# PA_stage_2.net
KiCad netlist of a schematic drawn in Altium Designer
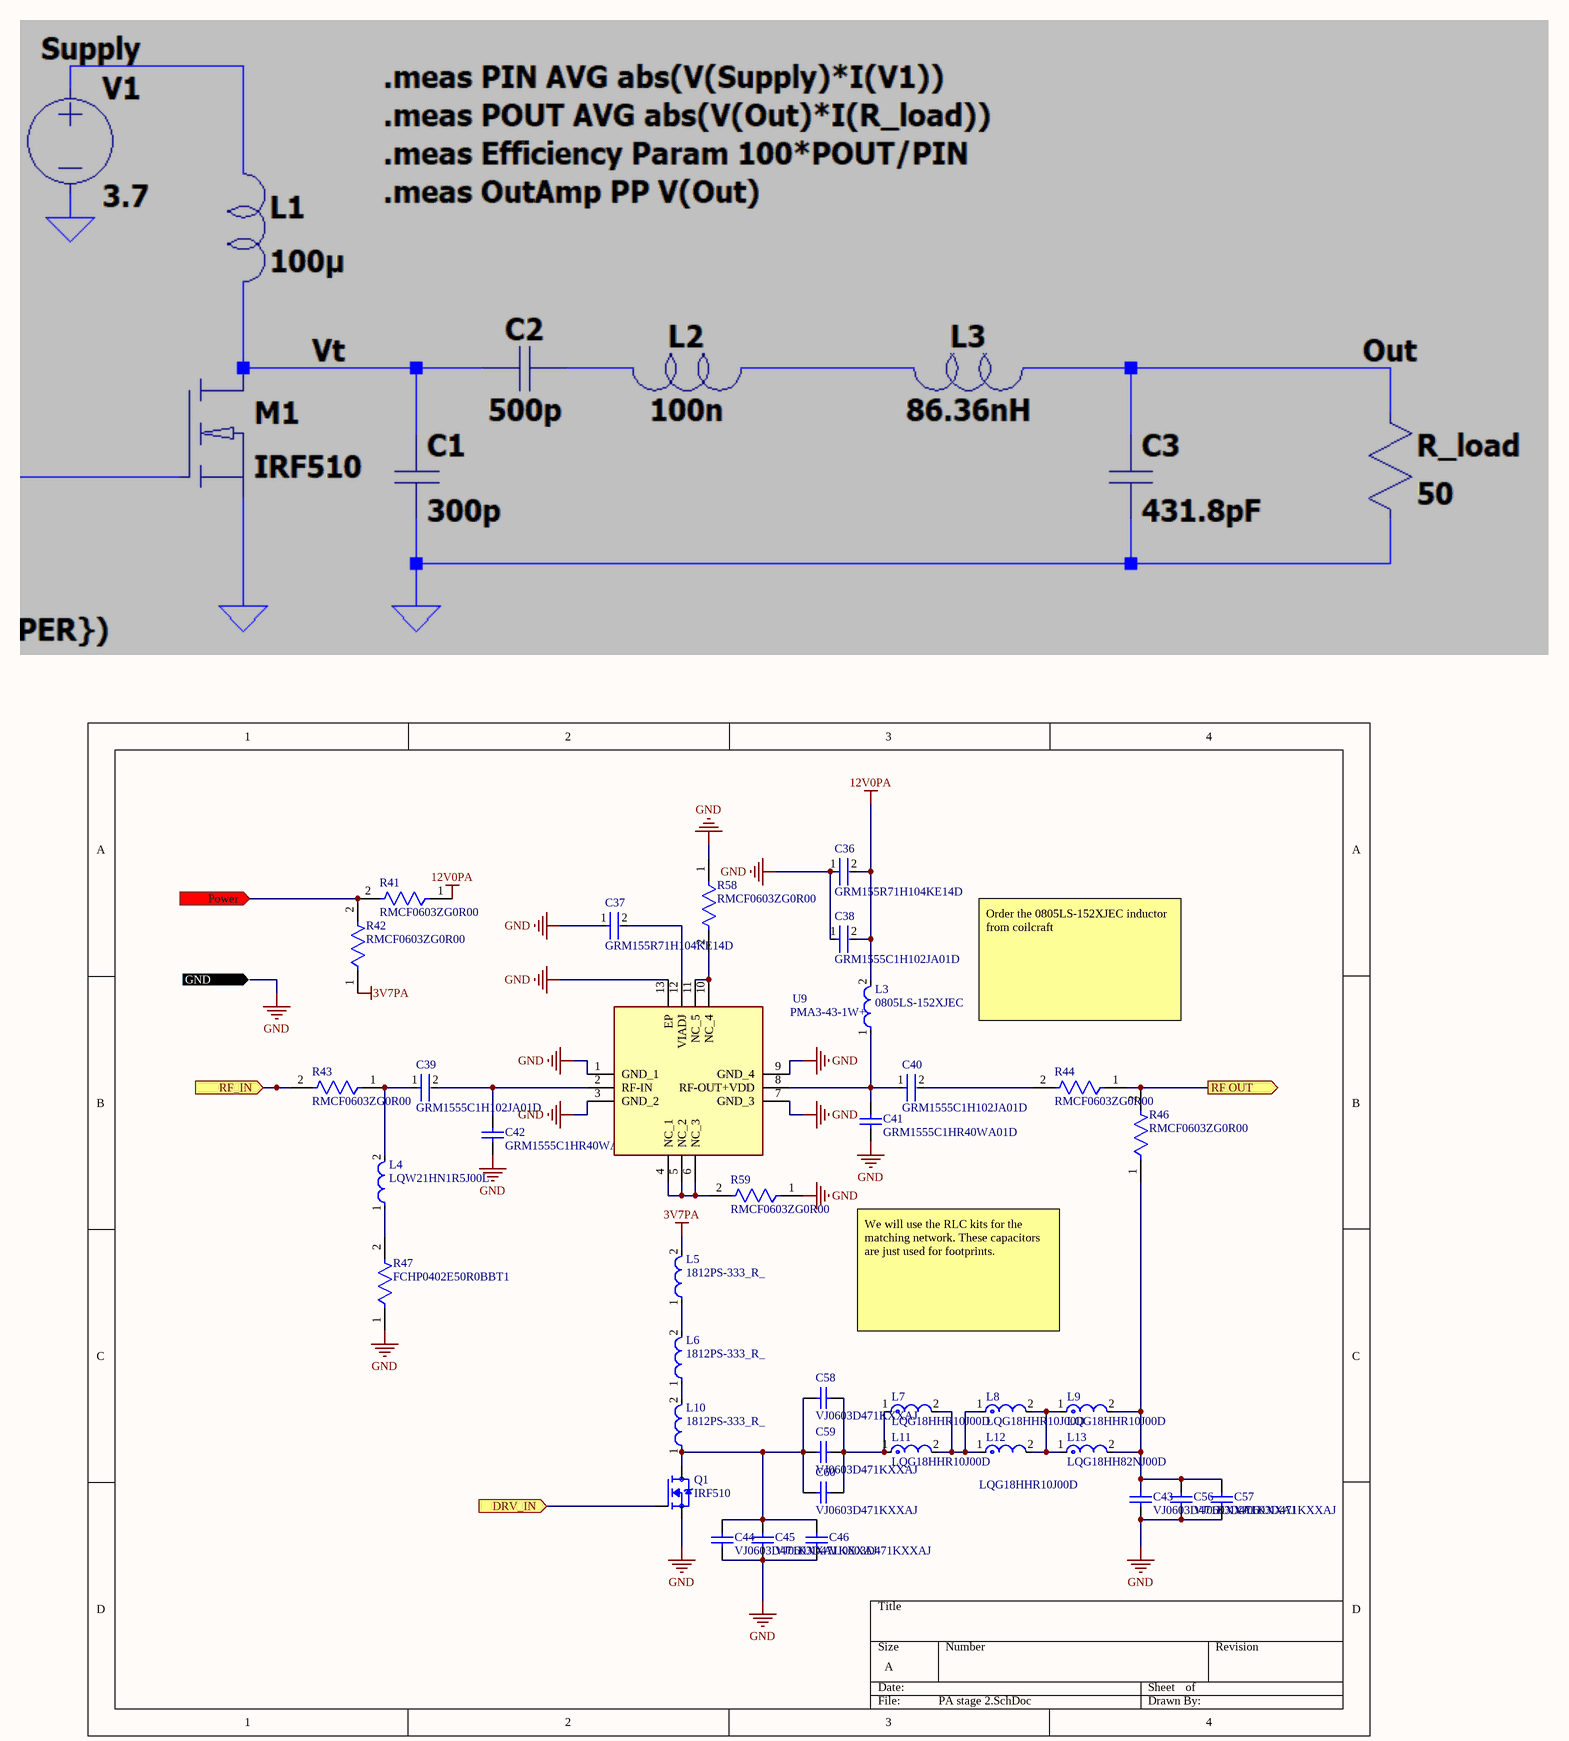
[diagram p0: PA stage 2.SchDoc]

(export (version "E")
  (design (tool "Eeschema 10.0.6"))
  (components
    (comp (ref "C36")
      (value "GRM155R71H104KE14D")
      (footprint "FP-GRM155-0_05-IPC_B")
      (description "Chip Multilayer Ceramic Capacitors for General Purpose, 0402, 0.10uF, X7R, 15%, 10%, 50V")
      (fields (field (name "VOLTAGE") "50V") (field (name "TOLERANCE") "10%"))
      (libsource (lib "Altium Content Vault") (part "02cd4be3c70576c341d710602a673aa"))
    )
    (comp (ref "C37")
      (value "GRM155R71H104KE14D")
      (footprint "FP-GRM155-0_05-IPC_B")
      (description "Chip Multilayer Ceramic Capacitors for General Purpose, 0402, 0.10uF, X7R, 15%, 10%, 50V")
      (fields (field (name "VOLTAGE") "50V") (field (name "TOLERANCE") "10%"))
      (libsource (lib "Altium Content Vault") (part "02cd4be3c70576c341d710602a673aa"))
    )
    (comp (ref "C38")
      (value "GRM1555C1H102JA01D")
      (footprint "FP-GRM155-0_05-IPC_B")
      (description "Chip Multilayer Ceramic Capacitors for General Purpose, 0402, 1000pF, C0G, 30ppm/°C, 5%, 50V")
      (fields (field (name "TOLERANCE") "5%") (field (name "VOLTAGE") "50V"))
      (libsource (lib "Altium Content Vault") (part "02cd4be3c70576c341d710602a673aa"))
    )
    (comp (ref "C39")
      (value "GRM1555C1H102JA01D")
      (footprint "FP-GRM155-0_05-IPC_B")
      (description "Chip Multilayer Ceramic Capacitors for General Purpose, 0402, 1000pF, C0G, 30ppm/°C, 5%, 50V")
      (fields (field (name "TOLERANCE") "5%") (field (name "VOLTAGE") "50V"))
      (libsource (lib "Altium Content Vault") (part "02cd4be3c70576c341d710602a673aa"))
    )
    (comp (ref "C40")
      (value "GRM1555C1H102JA01D")
      (footprint "FP-GRM155-0_05-IPC_B")
      (description "Chip Multilayer Ceramic Capacitors for General Purpose, 0402, 1000pF, C0G, 30ppm/°C, 5%, 50V")
      (fields (field (name "TOLERANCE") "5%") (field (name "VOLTAGE") "50V"))
      (libsource (lib "Altium Content Vault") (part "02cd4be3c70576c341d710602a673aa"))
    )
    (comp (ref "C41")
      (value "GRM1555C1HR40WA01D")
      (footprint "CAPC1005X55X25LL05T10")
      (fields (field (name "MANUFACTURER") "Murata"))
      (libsource (lib "Altium Content Vault") (part "CAP"))
    )
    (comp (ref "C42")
      (value "GRM1555C1HR40WA01D")
      (footprint "CAPC1005X55X25LL05T10")
      (fields (field (name "MANUFACTURER") "Murata"))
      (libsource (lib "Altium Content Vault") (part "CAP"))
    )
    (comp (ref "C43")
      (value "VJ0603D471KXXAJ")
      (footprint "CAPC1608X92X38LL15T08")
      (fields (field (name "MANUFACTURER") "Vitramon"))
      (libsource (lib "Altium Content Vault") (part "CAP"))
    )
    (comp (ref "C44")
      (value "VJ0603D471KXXAJ")
      (footprint "CAPC1608X92X38LL15T08")
      (fields (field (name "MANUFACTURER") "Vitramon"))
      (libsource (lib "Altium Content Vault") (part "CAP"))
    )
    (comp (ref "C45")
      (value "VJ0603D471KXXAJ")
      (footprint "CAPC1608X92X38LL15T08")
      (fields (field (name "MANUFACTURER") "Vitramon"))
      (libsource (lib "Altium Content Vault") (part "CAP"))
    )
    (comp (ref "C46")
      (value "VJ0603D471KXXAJ")
      (footprint "CAPC1608X92X38LL15T08")
      (fields (field (name "MANUFACTURER") "Vitramon"))
      (libsource (lib "Altium Content Vault") (part "CAP"))
    )
    (comp (ref "C56")
      (value "VJ0603D471KXXAJ")
      (footprint "CAPC1608X92X38LL15T08")
      (fields (field (name "MANUFACTURER") "Vitramon"))
      (libsource (lib "Altium Content Vault") (part "CAP"))
    )
    (comp (ref "C57")
      (value "VJ0603D471KXXAJ")
      (footprint "CAPC1608X92X38LL15T08")
      (fields (field (name "MANUFACTURER") "Vitramon"))
      (libsource (lib "Altium Content Vault") (part "CAP"))
    )
    (comp (ref "C58")
      (value "VJ0603D471KXXAJ")
      (footprint "CAPC1608X92X38LL15T08")
      (fields (field (name "MANUFACTURER") "Vitramon"))
      (libsource (lib "Altium Content Vault") (part "CAP"))
    )
    (comp (ref "C59")
      (value "VJ0603D471KXXAJ")
      (footprint "CAPC1608X92X38LL15T08")
      (fields (field (name "MANUFACTURER") "Vitramon"))
      (libsource (lib "Altium Content Vault") (part "CAP"))
    )
    (comp (ref "C60")
      (value "VJ0603D471KXXAJ")
      (footprint "CAPC1608X92X38LL15T08")
      (fields (field (name "MANUFACTURER") "Vitramon"))
      (libsource (lib "Altium Content Vault") (part "CAP"))
    )
    (comp (ref "L3")
      (value "0805LS-152XJEC")
      (footprint "FP-LQW21HN_00-MFG")
      (description "0805LS-152XJEC Coilcraft")
      (fields (field (name "TOLERANCE") "5%"))
      (libsource (lib "Altium Content Vault") (part "725321dda6339637d4d059423bc1c3c"))
    )
    (comp (ref "L4")
      (value "LQW21HN1R5J00L")
      (footprint "FP-LQW21HN_00-MFG")
      (description "Wire Wound Ferrite type RF Inuctor 1.5uH ±5% 85mA 5.33Ω 0805 (2012)")
      (fields (field (name "TOLERANCE") "5%"))
      (libsource (lib "Altium Content Vault") (part "725321dda6339637d4d059423bc1c3c"))
    )
    (comp (ref "L5")
      (value "1812PS-333_R_")
      (footprint "FP-1812PS-MFG")
      (description "1812PS-333_R_Coilcraft")
      (fields (field (name "TOLERANCE") "5%"))
      (libsource (lib "Altium Content Vault") (part "725321dda6339637d4d059423bc1c3c"))
    )
    (comp (ref "L6")
      (value "1812PS-333_R_")
      (footprint "FP-1812PS-MFG")
      (description "1812PS-333_R_Coilcraft")
      (fields (field (name "TOLERANCE") "5%"))
      (libsource (lib "Altium Content Vault") (part "725321dda6339637d4d059423bc1c3c"))
    )
    (comp (ref "L7")
      (value "LQG18HHR10J00D")
      (footprint "FP-LQG18HH_00-MFG")
      (description "Multilayer type Inductor for Automotive 100nH ±5% 0.9Ω 300mA 0603")
      (libsource (lib "Altium Content Vault") (part "4cc4b267dca4c8e51f7102f422741d8"))
    )
    (comp (ref "L8")
      (value "LQG18HHR10J00D")
      (footprint "FP-LQG18HH_00-MFG")
      (description "Multilayer type Inductor for Automotive 100nH ±5% 0.9Ω 300mA 0603")
      (libsource (lib "Altium Content Vault") (part "4cc4b267dca4c8e51f7102f422741d8"))
    )
    (comp (ref "L9")
      (value "LQG18HHR10J00D")
      (footprint "FP-LQG18HH_00-MFG")
      (description "Multilayer type Inductor for Automotive 100nH ±5% 0.9Ω 300mA 0603")
      (libsource (lib "Altium Content Vault") (part "4cc4b267dca4c8e51f7102f422741d8"))
    )
    (comp (ref "L10")
      (value "1812PS-333_R_")
      (footprint "FP-1812PS-MFG")
      (description "1812PS-333_R_ Coilcraft")
      (fields (field (name "TOLERANCE") "5%"))
      (libsource (lib "Altium Content Vault") (part "725321dda6339637d4d059423bc1c3c"))
    )
    (comp (ref "L11")
      (value "LQG18HHR10J00D")
      (footprint "FP-LQG18HH_00-MFG")
      (description "Multilayer type Inductor for Automotive 100nH ±5% 0.9Ω 300mA 0603")
      (libsource (lib "Altium Content Vault") (part "4cc4b267dca4c8e51f7102f422741d8"))
    )
    (comp (ref "L12")
      (value "LQG18HHR10J00D")
      (footprint "FP-LQG18HH_00-MFG")
      (description "Multilayer type Inductor for Automotive 100nH ±5% 0.9Ω 300mA 0603")
      (libsource (lib "Altium Content Vault") (part "4cc4b267dca4c8e51f7102f422741d8"))
    )
    (comp (ref "L13")
      (value "LQG18HH82NJ00D")
      (footprint "FP-LQG18HH_00-IPC_B")
      (description "Multilayer type Inductor for Automotive 82nH ±5% 0.85Ω 300mA 0603")
      (libsource (lib "Altium Content Vault") (part "4cc4b267dca4c8e51f7102f422741d8"))
    )
    (comp (ref "Q1")
      (value "IRF510")
      (footprint "TO254P1051X465X1931-3")
      (description "N-Channel 100 V 5.6A (Tc) 3.7W (Ta), 43W (Tc) Surface Mount DÂ²PAK (TO-263)")
      (fields (field (name "MF") "Vishay Siliconix"))
      (libsource (lib "IRF510") (part "IRF510"))
    )
    (comp (ref "R41")
      (value "RMCF0603ZG0R00")
      (footprint "FP-RMCF0603-IPC_B")
      (description "0Ω ±0 0.1W 0603 Thick Film Chip Resistor AEC-Q200 compliant")
      (libsource (lib "Altium Content Vault") (part "1029c3af85768c4190bb7ad29bc67b5"))
    )
    (comp (ref "R42")
      (value "RMCF0603ZG0R00")
      (footprint "FP-RMCF0603-IPC_B")
      (description "0Ω ±0 0.1W 0603 Thick Film Chip Resistor AEC-Q200 compliant")
      (libsource (lib "Altium Content Vault") (part "1029c3af85768c4190bb7ad29bc67b5"))
    )
    (comp (ref "R43")
      (value "RMCF0603ZG0R00")
      (footprint "FP-RMCF0603-IPC_B")
      (description "0Ω ±0 0.1W 0603 Thick Film Chip Resistor AEC-Q200 compliant")
      (libsource (lib "Altium Content Vault") (part "1029c3af85768c4190bb7ad29bc67b5"))
    )
    (comp (ref "R44")
      (value "RMCF0603ZG0R00")
      (footprint "FP-RMCF0603-IPC_B")
      (description "0Ω ±0 0.1W 0603 Thick Film Chip Resistor AEC-Q200 compliant")
      (libsource (lib "Altium Content Vault") (part "1029c3af85768c4190bb7ad29bc67b5"))
    )
    (comp (ref "R46")
      (value "RMCF0603ZG0R00")
      (footprint "FP-RMCF0603-IPC_B")
      (description "0Ω ±0 0.1W 0603 Thick Film Chip Resistor AEC-Q200 compliant")
      (libsource (lib "Altium Content Vault") (part "1029c3af85768c4190bb7ad29bc67b5"))
    )
    (comp (ref "R47")
      (value "FCHP0402E50R0BBT1")
      (footprint "FP-FC0402-MFG")
      (fields (field (name "TOLERANCE") "0.1%"))
      (libsource (lib "Altium Content Vault") (part "1029c3af85768c4190bb7ad29bc67b5"))
    )
    (comp (ref "R58")
      (value "RMCF0603ZG0R00")
      (footprint "FP-RMCF0603-IPC_B")
      (description "0Ω ±0 0.1W 0603 Thick Film Chip Resistor AEC-Q200 compliant")
      (libsource (lib "Altium Content Vault") (part "1029c3af85768c4190bb7ad29bc67b5"))
    )
    (comp (ref "R59")
      (value "RMCF0603ZG0R00")
      (footprint "FP-RMCF0603-IPC_B")
      (description "0Ω ±0 0.1W 0603 Thick Film Chip Resistor AEC-Q200 compliant")
      (libsource (lib "Altium Content Vault") (part "1029c3af85768c4190bb7ad29bc67b5"))
    )
    (comp (ref "U9")
      (value "PMA3-43-1W+")
      (footprint "QFN51P300X300X89-13N")
      (description "Integrated Circuit")
      (libsource (lib "SamacSys") (part "PMA3-43-1W+"))
    )
  )
  (nets
    (net (code "1") (name "/DRV_IN") (class "Default")
      (node (ref "Q1") (pin "1") (pinfunction "G_1") (pintype "passive"))
    )
    (net (code "2") (name "/Power") (class "Default")
      (node (ref "R41") (pin "2") (pinfunction "2_2") (pintype "passive"))
      (node (ref "R42") (pin "2") (pinfunction "2_2") (pintype "passive"))
    )
    (net (code "3") (name "/RF OUT") (class "Default")
      (node (ref "R44") (pin "1") (pinfunction "1_1") (pintype "passive"))
      (node (ref "R46") (pin "2") (pinfunction "2_2") (pintype "passive"))
    )
    (net (code "4") (name "/RF_IN") (class "Default")
      (node (ref "R43") (pin "2") (pinfunction "2_2") (pintype "passive"))
    )
    (net (code "5") (name "3V7PA") (class "Default")
      (node (ref "L5") (pin "2") (pinfunction "2_2") (pintype "passive"))
      (node (ref "R42") (pin "1") (pinfunction "1_1") (pintype "passive"))
    )
    (net (code "6") (name "12V0PA") (class "Default")
      (node (ref "C36") (pin "2") (pinfunction "2_2") (pintype "passive"))
      (node (ref "C38") (pin "2") (pinfunction "2_2") (pintype "passive"))
      (node (ref "L3") (pin "2") (pinfunction "2_2") (pintype "passive"))
      (node (ref "R41") (pin "1") (pinfunction "1_1") (pintype "passive"))
    )
    (net (code "7") (name "GND") (class "Default")
      (node (ref "C36") (pin "1") (pinfunction "1_1") (pintype "passive"))
      (node (ref "C37") (pin "1") (pinfunction "1_1") (pintype "passive"))
      (node (ref "C38") (pin "1") (pinfunction "1_1") (pintype "passive"))
      (node (ref "C41") (pin "1") (pinfunction "1_1") (pintype "passive"))
      (node (ref "C42") (pin "1") (pinfunction "1_1") (pintype "passive"))
      (node (ref "C43") (pin "1") (pinfunction "1_1") (pintype "passive"))
      (node (ref "C44") (pin "1") (pinfunction "1_1") (pintype "passive"))
      (node (ref "C45") (pin "1") (pinfunction "1_1") (pintype "passive"))
      (node (ref "C46") (pin "1") (pinfunction "1_1") (pintype "passive"))
      (node (ref "C56") (pin "1") (pinfunction "1_1") (pintype "passive"))
      (node (ref "C57") (pin "1") (pinfunction "1_1") (pintype "passive"))
      (node (ref "Q1") (pin "3") (pinfunction "S_3") (pintype "passive"))
      (node (ref "R47") (pin "1") (pinfunction "1_1") (pintype "passive"))
      (node (ref "R58") (pin "1") (pinfunction "1_1") (pintype "passive"))
      (node (ref "R59") (pin "1") (pinfunction "1_1") (pintype "passive"))
      (node (ref "U9") (pin "1") (pinfunction "GND_1_1") (pintype "passive"))
      (node (ref "U9") (pin "13") (pinfunction "EP_13") (pintype "passive"))
      (node (ref "U9") (pin "3") (pinfunction "GND_2_3") (pintype "passive"))
      (node (ref "U9") (pin "7") (pinfunction "GND_3_7") (pintype "passive"))
      (node (ref "U9") (pin "9") (pinfunction "GND_4_9") (pintype "passive"))
    )
    (net (code "8") (name "Net-(C39-Pad1)") (class "Default")
      (node (ref "C39") (pin "1") (pinfunction "1_1") (pintype "passive"))
      (node (ref "L4") (pin "2") (pinfunction "2_2") (pintype "passive"))
      (node (ref "R43") (pin "1") (pinfunction "1_1") (pintype "passive"))
    )
    (net (code "9") (name "Net-(C40-Pad2)") (class "Default")
      (node (ref "C40") (pin "2") (pinfunction "2_2") (pintype "passive"))
      (node (ref "R44") (pin "2") (pinfunction "2_2") (pintype "passive"))
    )
    (net (code "10") (name "Net-(C43-Pad2)") (class "Default")
      (node (ref "C43") (pin "2") (pinfunction "2_2") (pintype "passive"))
      (node (ref "C56") (pin "2") (pinfunction "2_2") (pintype "passive"))
      (node (ref "C57") (pin "2") (pinfunction "2_2") (pintype "passive"))
      (node (ref "L13") (pin "2") (pinfunction "2_2") (pintype "passive"))
      (node (ref "L9") (pin "2") (pinfunction "2_2") (pintype "passive"))
      (node (ref "R46") (pin "1") (pinfunction "1_1") (pintype "passive"))
    )
    (net (code "11") (name "Net-(C58-Pad1)") (class "Default")
      (node (ref "C58") (pin "1") (pinfunction "1_1") (pintype "passive"))
      (node (ref "C59") (pin "1") (pinfunction "1_1") (pintype "passive"))
      (node (ref "C60") (pin "1") (pinfunction "1_1") (pintype "passive"))
      (node (ref "L11") (pin "1") (pinfunction "1_1") (pintype "passive"))
      (node (ref "L7") (pin "1") (pinfunction "1_1") (pintype "passive"))
    )
    (net (code "12") (name "Net-(L4-Pad1)") (class "Default")
      (node (ref "L4") (pin "1") (pinfunction "1_1") (pintype "passive"))
      (node (ref "R47") (pin "2") (pinfunction "2_2") (pintype "passive"))
    )
    (net (code "13") (name "Net-(L5-Pad1)") (class "Default")
      (node (ref "L5") (pin "1") (pinfunction "1_1") (pintype "passive"))
      (node (ref "L6") (pin "2") (pinfunction "2_2") (pintype "passive"))
    )
    (net (code "14") (name "Net-(L10-Pad2)") (class "Default")
      (node (ref "L10") (pin "2") (pinfunction "2_2") (pintype "passive"))
      (node (ref "L6") (pin "1") (pinfunction "1_1") (pintype "passive"))
    )
    (net (code "15") (name "Net-(L11-Pad2)") (class "Default")
      (node (ref "L11") (pin "2") (pinfunction "2_2") (pintype "passive"))
      (node (ref "L12") (pin "1") (pinfunction "1_1") (pintype "passive"))
      (node (ref "L7") (pin "2") (pinfunction "2_2") (pintype "passive"))
      (node (ref "L8") (pin "1") (pinfunction "1_1") (pintype "passive"))
    )
    (net (code "16") (name "Net-(L12-Pad2)") (class "Default")
      (node (ref "L12") (pin "2") (pinfunction "2_2") (pintype "passive"))
      (node (ref "L13") (pin "1") (pinfunction "1_1") (pintype "passive"))
      (node (ref "L8") (pin "2") (pinfunction "2_2") (pintype "passive"))
      (node (ref "L9") (pin "1") (pinfunction "1_1") (pintype "passive"))
    )
    (net (code "17") (name "Net-(Q1-D)") (class "Default")
      (node (ref "C44") (pin "2") (pinfunction "2_2") (pintype "passive"))
      (node (ref "C45") (pin "2") (pinfunction "2_2") (pintype "passive"))
      (node (ref "C46") (pin "2") (pinfunction "2_2") (pintype "passive"))
      (node (ref "C58") (pin "2") (pinfunction "2_2") (pintype "passive"))
      (node (ref "C59") (pin "2") (pinfunction "2_2") (pintype "passive"))
      (node (ref "C60") (pin "2") (pinfunction "2_2") (pintype "passive"))
      (node (ref "L10") (pin "1") (pinfunction "1_1") (pintype "passive"))
      (node (ref "Q1") (pin "2") (pinfunction "D_2") (pintype "passive"))
    )
    (net (code "18") (name "Net-(U9-NC_1)") (class "Default")
      (node (ref "R59") (pin "2") (pinfunction "2_2") (pintype "passive"))
      (node (ref "U9") (pin "4") (pinfunction "NC_1_4") (pintype "passive"))
      (node (ref "U9") (pin "5") (pinfunction "NC_2_5") (pintype "passive"))
      (node (ref "U9") (pin "6") (pinfunction "NC_3_6") (pintype "passive"))
    )
    (net (code "19") (name "Net-(U9-NC_4)") (class "Default")
      (node (ref "R58") (pin "2") (pinfunction "2_2") (pintype "passive"))
      (node (ref "U9") (pin "10") (pinfunction "NC_4_10") (pintype "passive"))
      (node (ref "U9") (pin "11") (pinfunction "NC_5_11") (pintype "passive"))
    )
    (net (code "20") (name "Net-(U9-RF-IN)") (class "Default")
      (node (ref "C39") (pin "2") (pinfunction "2_2") (pintype "passive"))
      (node (ref "C42") (pin "2") (pinfunction "2_2") (pintype "passive"))
      (node (ref "U9") (pin "2") (pinfunction "RF-IN_2") (pintype "passive"))
    )
    (net (code "21") (name "Net-(U9-RF-OUT+VDD)") (class "Default")
      (node (ref "C40") (pin "1") (pinfunction "1_1") (pintype "passive"))
      (node (ref "C41") (pin "2") (pinfunction "2_2") (pintype "passive"))
      (node (ref "L3") (pin "1") (pinfunction "1_1") (pintype "passive"))
      (node (ref "U9") (pin "8") (pinfunction "RF-OUT+VDD_8") (pintype "passive"))
    )
    (net (code "22") (name "Net-(U9-VIADJ)") (class "Default")
      (node (ref "C37") (pin "2") (pinfunction "2_2") (pintype "passive"))
      (node (ref "U9") (pin "12") (pinfunction "VIADJ_12") (pintype "passive"))
    )
  )
)
